# SAMPLE.net
KiCad netlist of a schematic drawn in Altium Designer
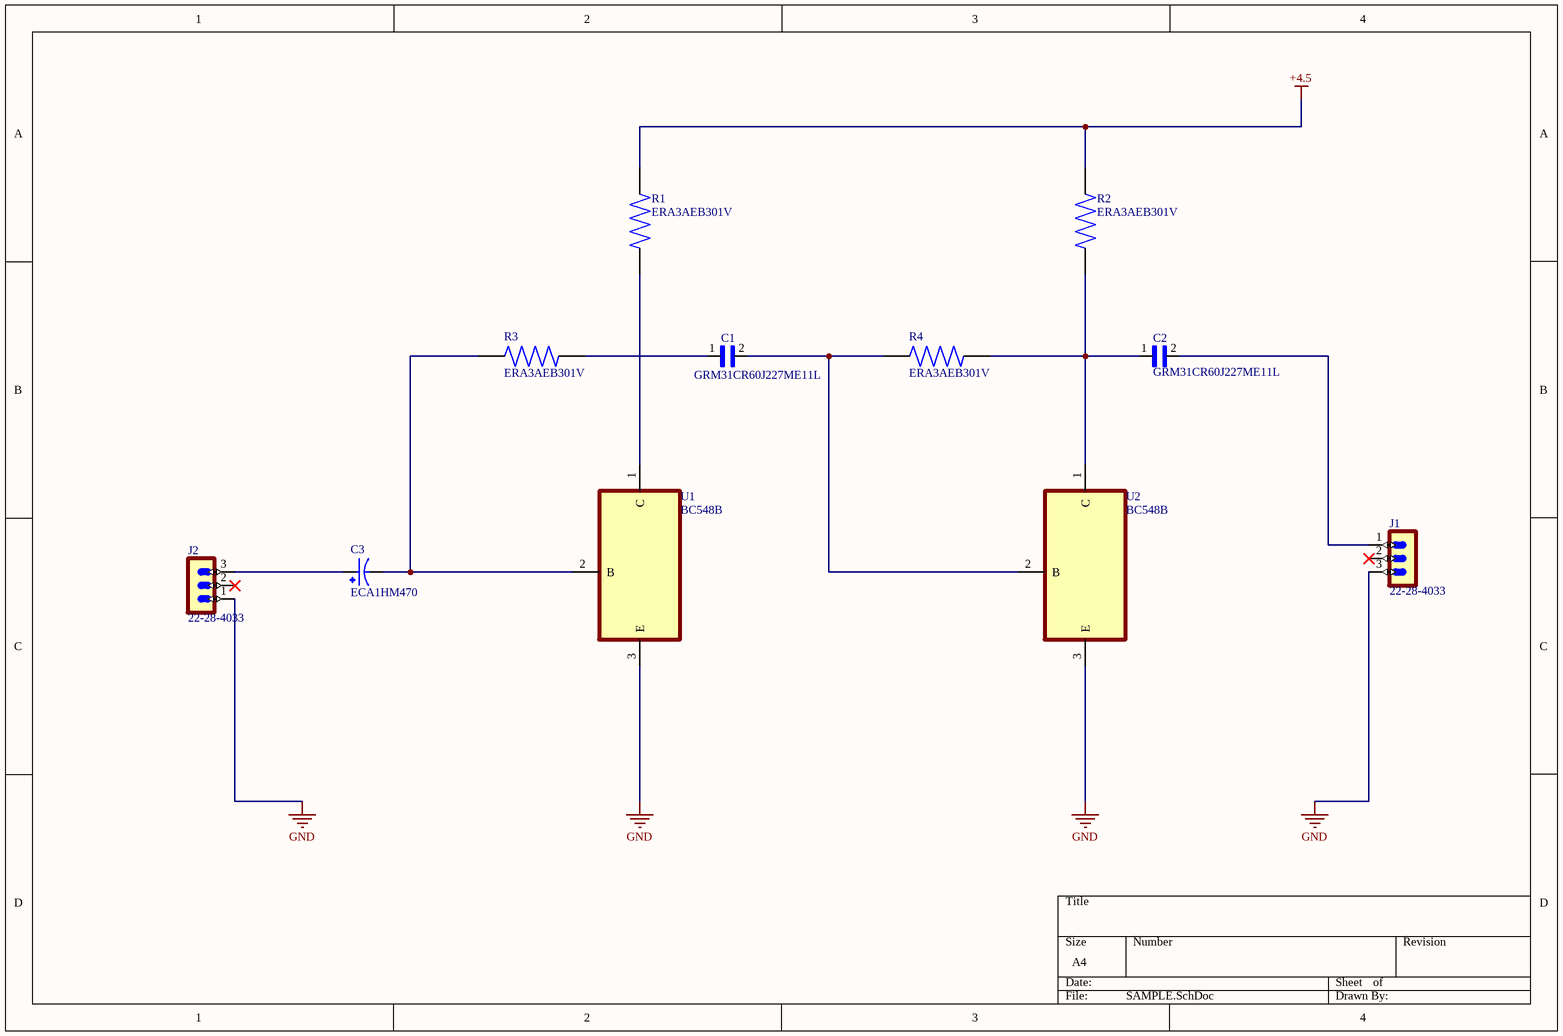
[diagram p0: SAMPLE.SchDoc]

(export (version "E")
  (design (tool "Eeschema 10.0.6"))
  (components
    (comp (ref "C1")
      (value "GRM31CR60J227ME11L")
      (footprint "CAPC3216X190N")
      (description "SMD Multilayer Ceramic Capacitor, GRM Series, 220 F, 20%, X5R, 6.3 V, 1206 [3216 Metric]")
      (fields (field (name "DIGI-KEY_PART_NUMBER") "490-13970-1-ND") (field (name "MF") "Murata Electronics"))
      (libsource (lib "GRM31CR60J227ME11L") (part "GRM31CR60J227ME11L"))
    )
    (comp (ref "C2")
      (value "GRM31CR60J227ME11L")
      (footprint "CAPC3216X190N")
      (description "SMD Multilayer Ceramic Capacitor, GRM Series, 220 F, 20%, X5R, 6.3 V, 1206 [3216 Metric]")
      (fields (field (name "DIGI-KEY_PART_NUMBER") "490-13970-1-ND") (field (name "MF") "Murata Electronics"))
      (libsource (lib "GRM31CR60J227ME11L") (part "GRM31CR60J227ME11L"))
    )
    (comp (ref "C3")
      (value "ECA1HM470")
      (footprint "CAPPRD250W50D630H1120")
      (description "47ÂµF 50V Aluminum Electrolytic Capacitors Radial, Can 2000 Hrs @ 85Â°C")
      (fields (field (name "MF") "Panasonic Electronic"))
      (libsource (lib "ECA1HM470") (part "ECA1HM470"))
    )
    (comp (ref "J1")
      (value "22-28-4033")
      (footprint "1X03-PIN")
      (description "Connector Header Through Hole 3 position 0.100 (2.54mm)")
      (fields (field (name "MF") "Molex") (field (name "MP") "22284033"))
      (libsource (lib "22-28-4033") (part "22-28-4033"))
    )
    (comp (ref "J2")
      (value "22-28-4033")
      (footprint "1X03-PIN")
      (description "Connector Header Through Hole 3 position 0.100 (2.54mm)")
      (fields (field (name "MF") "Molex") (field (name "MP") "22284033"))
      (libsource (lib "") (part "22-28-4033_1"))
    )
    (comp (ref "R1")
      (value "ERA3AEB301V")
      (footprint "RES_ERA3AEB301V")
      (libsource (lib "ERA3AEB301V") (part "ERA3AEB301V"))
    )
    (comp (ref "R2")
      (value "ERA3AEB301V")
      (footprint "RES_ERA3AEB301V")
      (libsource (lib "ERA3AEB301V") (part "ERA3AEB301V"))
    )
    (comp (ref "R3")
      (value "ERA3AEB301V")
      (footprint "RES_ERA3AEB301V")
      (libsource (lib "ERA3AEB301V") (part "ERA3AEB301V"))
    )
    (comp (ref "R4")
      (value "ERA3AEB301V")
      (footprint "RES_ERA3AEB301V")
      (libsource (lib "ERA3AEB301V") (part "ERA3AEB301V"))
    )
    (comp (ref "U1")
      (value "BC548B")
      (footprint "TO127P254X732-3")
      (description "Transistor bipolar _BJT_ NPN 30V 100mA 300MHz 625mW Agujero pasante TO-92-3")
      (fields (field (name "MF") "ON Semiconductor"))
      (libsource (lib "BC548B") (part "BC548B"))
    )
    (comp (ref "U2")
      (value "BC548B")
      (footprint "TO127P254X732-3")
      (description "Transistor bipolar _BJT_ NPN 30V 100mA 300MHz 625mW Agujero pasante TO-92-3")
      (fields (field (name "MF") "ON Semiconductor"))
      (libsource (lib "BC548B") (part "BC548B"))
    )
  )
  (nets
    (net (code "1") (name "+4.5") (class "Default")
      (node (ref "R1") (pin "2") (pinfunction "2_2") (pintype "passive"))
      (node (ref "R2") (pin "2") (pinfunction "2_2") (pintype "passive"))
    )
    (net (code "2") (name "GND") (class "Default")
      (node (ref "J1") (pin "3") (pinfunction "3_3") (pintype "bidirectional"))
      (node (ref "J2") (pin "1") (pinfunction "1_1") (pintype "bidirectional"))
      (node (ref "U1") (pin "3") (pinfunction "E_3") (pintype "passive"))
      (node (ref "U2") (pin "3") (pinfunction "E_3") (pintype "passive"))
    )
    (net (code "3") (name "Net-(C1-Pad1)") (class "Default")
      (node (ref "C1") (pin "1") (pinfunction "1_1") (pintype "passive"))
      (node (ref "R3") (pin "2") (pinfunction "2_2") (pintype "passive"))
    )
    (net (code "4") (name "Net-(C2-Pad2)") (class "Default")
      (node (ref "C2") (pin "2") (pinfunction "2_2") (pintype "passive"))
      (node (ref "J1") (pin "1") (pinfunction "1_1") (pintype "bidirectional"))
    )
    (net (code "5") (name "Net-(C3-PadP)") (class "Default")
      (node (ref "C3") (pin "P") (pinfunction "P_P") (pintype "passive"))
      (node (ref "J2") (pin "3") (pinfunction "3_3") (pintype "bidirectional"))
    )
    (net (code "6") (name "Net-(U1-B)") (class "Default")
      (node (ref "C3") (pin "N") (pinfunction "N_N") (pintype "passive"))
      (node (ref "R3") (pin "1") (pinfunction "1_1") (pintype "passive"))
      (node (ref "U1") (pin "2") (pinfunction "B_2") (pintype "passive"))
    )
    (net (code "7") (name "Net-(U1-C)") (class "Default")
      (node (ref "R1") (pin "1") (pinfunction "1_1") (pintype "passive"))
      (node (ref "U1") (pin "1") (pinfunction "C_1") (pintype "passive"))
    )
    (net (code "8") (name "Net-(U2-B)") (class "Default")
      (node (ref "C1") (pin "2") (pinfunction "2_2") (pintype "passive"))
      (node (ref "R4") (pin "1") (pinfunction "1_1") (pintype "passive"))
      (node (ref "U2") (pin "2") (pinfunction "B_2") (pintype "passive"))
    )
    (net (code "9") (name "Net-(U2-C)") (class "Default")
      (node (ref "C2") (pin "1") (pinfunction "1_1") (pintype "passive"))
      (node (ref "R2") (pin "1") (pinfunction "1_1") (pintype "passive"))
      (node (ref "R4") (pin "2") (pinfunction "2_2") (pintype "passive"))
      (node (ref "U2") (pin "1") (pinfunction "C_1") (pintype "passive"))
    )
    (net (code "10") (name "unconnected-(J1-Pad2)") (class "Default")
      (node (ref "J1") (pin "2") (pinfunction "2_2") (pintype "bidirectional+no_connect"))
    )
    (net (code "11") (name "unconnected-(J2-Pad2)") (class "Default")
      (node (ref "J2") (pin "2") (pinfunction "2_2") (pintype "bidirectional+no_connect"))
    )
  )
)
